# PCBSchematic.net
KiCad netlist of a schematic drawn in Altium Designer
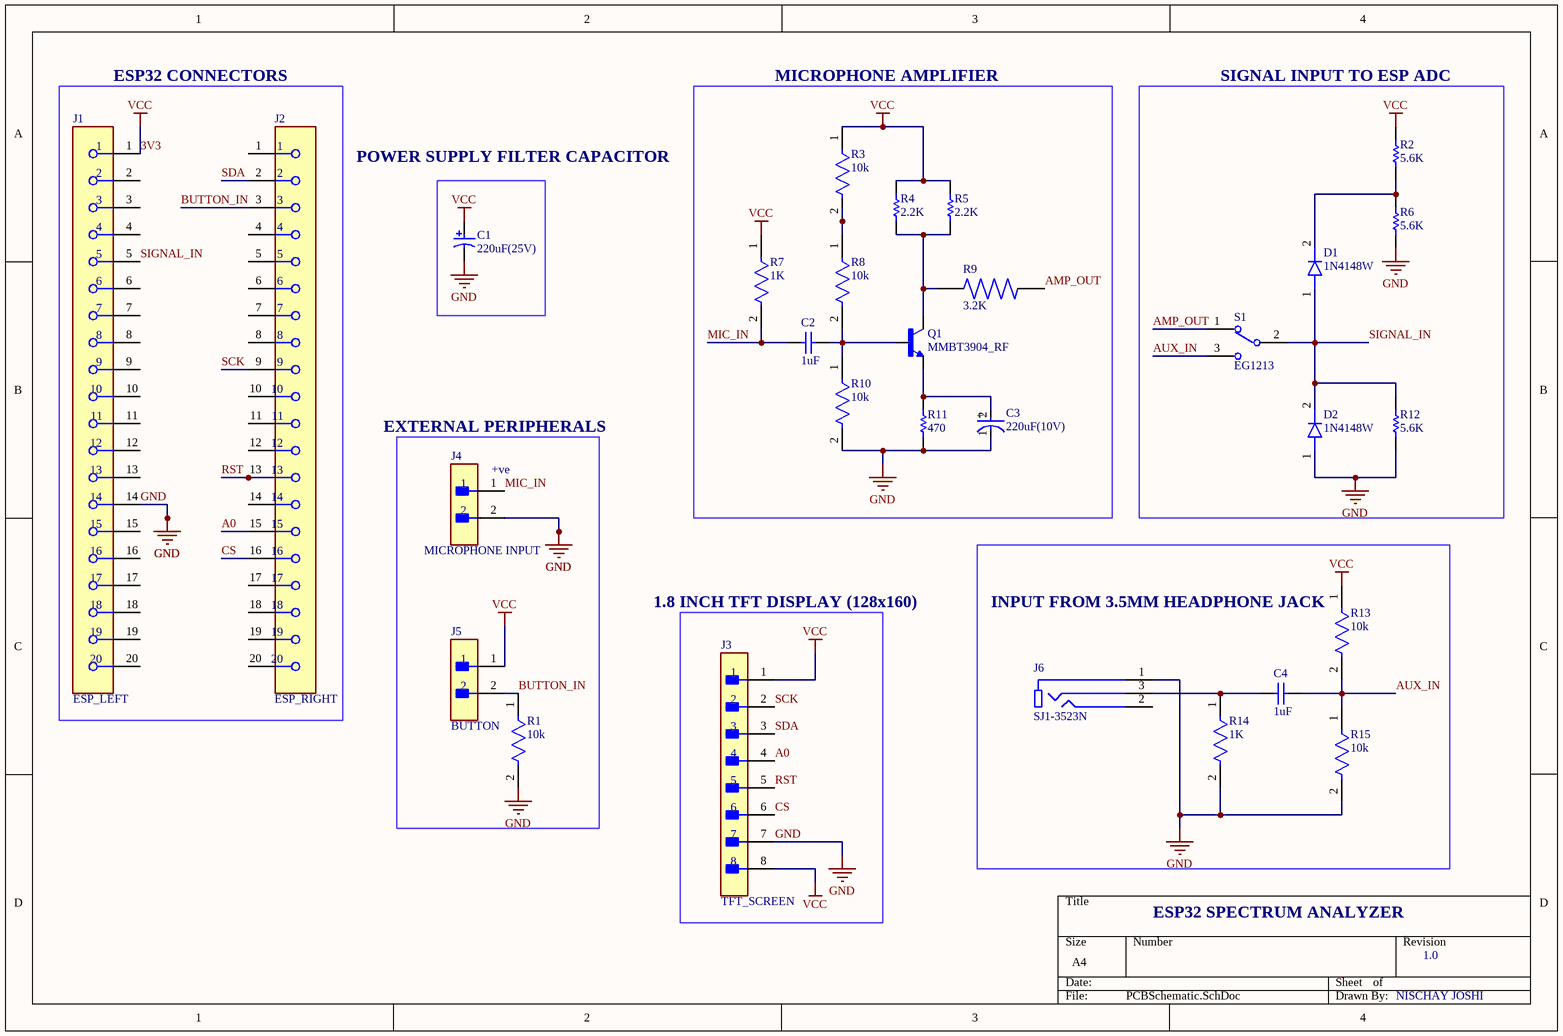
[diagram p0: PCBSchematic.SchDoc]

(export (version "E")
  (design (tool "Eeschema 10.0.6"))
  (components
    (comp (ref "C1")
      (value "220uF(25V)")
      (footprint "PNSC-EEE-FK1E221P_N")
      (fields (field (name "MANUFACTURER") "Panasonic"))
      (libsource (lib "Altium Content Vault") (part "CAP-P-2"))
    )
    (comp (ref "C2")
      (value "1uF")
      (footprint "CAPC3216X110X50LL20T25")
      (description "Chip Capacitor, 1 uF, +/- 10%, 50 V, -55 to 125 degC, 1206 (3216 Metric), RoHS, Tape and Reel")
      (fields (field (name "MANUFACTURER") "Kemet") (field (name "TOLERANCE") "10%"))
      (libsource (lib "Altium Content Vault") (part "CAP-NP-2"))
    )
    (comp (ref "C3")
      (value "220uF(10V)")
      (footprint "FP-TAJD-MFG")
      (description "220uF 10V  ±10% 500mΩ 2917  SMD Tantalum Capacitor")
      (fields (field (name "TOLERANCE") "10%") (field (name "VOLTAGE") "10V"))
      (libsource (lib "Altium Content Vault") (part "a00bbbee19879c290e62620ae7e47b1"))
    )
    (comp (ref "C4")
      (value "1uF")
      (footprint "CAPC3216X110X50LL20T25")
      (description "Chip Capacitor, 1 uF, +/- 10%, 50 V, -55 to 125 degC, 1206 (3216 Metric), RoHS, Tape and Reel")
      (fields (field (name "MANUFACTURER") "Kemet") (field (name "TOLERANCE") "10%"))
      (libsource (lib "Altium Content Vault") (part "CAP-NP-2"))
    )
    (comp (ref "D1")
      (value "1N4148W")
      (footprint "1N4148W:SOD523F")
      (fields (field (name "MF") "{'manufacturer': u'Diotec Semiconductor'}"))
      (libsource (lib "*") (part "1N4148W"))
    )
    (comp (ref "D2")
      (value "1N4148W")
      (footprint "1N4148W:SOD523F")
      (fields (field (name "MF") "{'manufacturer': u'Diotec Semiconductor'}"))
      (libsource (lib "*") (part "1N4148W"))
    )
    (comp (ref "J1")
      (value "ESP_LEFT")
      (footprint "FP-ESQ-120-14-G-S-MFG")
      (description "CONN SOCKET 20POS 0.1 GOLD PCB")
      (libsource (lib "Altium Content Vault") (part "dba14e038e6f7492952b7f1e871f183"))
    )
    (comp (ref "J2")
      (value "ESP_RIGHT")
      (footprint "FP-ESQ-120-14-G-S-MFG")
      (description "CONN SOCKET 20POS 0.1 GOLD PCB")
      (libsource (lib "Altium Content Vault") (part "dba14e038e6f7492952b7f1e871f183"))
    )
    (comp (ref "J3")
      (value "TFT_SCREEN")
      (footprint "FP-M20-9990846-MFG")
      (description "CONN HEADER VERT 8POS 2.54MM")
      (libsource (lib "Altium Content Vault") (part "99ec2b232beb5d2356d4d77f6a047f0"))
    )
    (comp (ref "J4")
      (value "MICROPHONE INPUT")
      (footprint "FP-M20-9990246-MFG")
      (description "CONN HEADER VERT 2POS 2.54MM")
      (fields
        (field (name "OCTOPART") "https://octopart.com/m20-9990246-harwin-2590635")
        (field (name "MANUFACTURER") "Harwin")
      )
      (libsource (lib "Altium Content Vault") (part "3bc925449376181038e59eaffc5286c"))
    )
    (comp (ref "J5")
      (value "BUTTON")
      (footprint "FP-M20-9990246-MFG")
      (description "CONN HEADER VERT 2POS 2.54MM")
      (fields
        (field (name "OCTOPART") "https://octopart.com/m20-9990246-harwin-2590635")
        (field (name "MANUFACTURER") "Harwin")
      )
      (libsource (lib "Altium Content Vault") (part "3bc925449376181038e59eaffc5286c"))
    )
    (comp (ref "J6")
      (value "SJ1-3523N")
      (footprint "SJ1-3523N:CUI_SJ1-3523N")
      (description "3.5 mm Right-Angle Stereo Jack, 3 Pin PCB Mount, Non-Threaded")
      (fields (field (name "MF") "{'manufacturer': u'CUI Devices'}"))
      (libsource (lib "*") (part "SJ1-3523N"))
    )
    (comp (ref "Q1")
      (value "MMBT3904_RF")
      (footprint "MMBT3904 RF:SOT95P237X112-3N")
      (description "Bipolar (BJT) Transistor NPN 65 V 100 mA 100MHz 200 mW Surface Mount SOT-23")
      (fields (field (name "MF") "{'manufacturer': u'Taiwan Semiconductor'}"))
      (libsource (lib "*") (part "MMBT3904_RF"))
    )
    (comp (ref "R1")
      (value "10k")
      (footprint "FP-RMCF2512-IPC_C")
      (description "10kΩ ±5% 1W 2512 Thick Film Chip Resistor AEC-Q200 compliant")
      (fields (field (name "TOLERANCE") "5%"))
      (libsource (lib "Altium Content Vault") (part "1029c3af85768c4190bb7ad29bc67b5"))
    )
    (comp (ref "R2")
      (value "5.6K")
      (footprint "RESC3216X60X45LL10T20")
      (fields (field (name "MANUFACTURER") "Vishay Dale") (field (name "PART NUMBER") "CRCW12065K60FKEA"))
      (libsource (lib "Altium Content Vault") (part "RES"))
    )
    (comp (ref "R3")
      (value "10k")
      (footprint "FP-RMCF2512-IPC_C")
      (description "10kΩ ±5% 1W 2512 Thick Film Chip Resistor AEC-Q200 compliant")
      (fields (field (name "TOLERANCE") "5%"))
      (libsource (lib "Altium Content Vault") (part "1029c3af85768c4190bb7ad29bc67b5"))
    )
    (comp (ref "R4")
      (value "2.2K")
      (footprint "RESC3116X65X40ML10T20")
      (description "Chip Resistor, 2.2 KOhm, +/- 1%, 250 mW, -55 to 155 degC, 1206 (3216 Metric), RoHS, Tape and Reel")
      (fields (field (name "MANUFACTURER") "Yageo") (field (name "TOLERANCE") "1%"))
      (libsource (lib "Altium Content Vault") (part "RES-2"))
    )
    (comp (ref "R5")
      (value "2.2K")
      (footprint "RESC3116X65X40ML10T20")
      (description "Chip Resistor, 2.2 KOhm, +/- 1%, 250 mW, -55 to 155 degC, 1206 (3216 Metric), RoHS, Tape and Reel")
      (fields (field (name "MANUFACTURER") "Yageo") (field (name "TOLERANCE") "1%"))
      (libsource (lib "Altium Content Vault") (part "RES-2"))
    )
    (comp (ref "R6")
      (value "5.6K")
      (footprint "RESC3216X60X45LL10T20")
      (fields (field (name "MANUFACTURER") "Vishay Dale") (field (name "PART NUMBER") "CRCW12065K60FKEA"))
      (libsource (lib "Altium Content Vault") (part "RES"))
    )
    (comp (ref "R7")
      (value "1K")
      (footprint "FP-CRCW2512-e3-IPC_C")
      (description "RES Thick Film, 1kΩ, 1%, 1W, 100ppm/°C, 2512")
      (fields (field (name "TOLERANCE") "1%"))
      (libsource (lib "Altium Content Vault") (part "1029c3af85768c4190bb7ad29bc67b5"))
    )
    (comp (ref "R8")
      (value "10k")
      (footprint "FP-RMCF2512-IPC_C")
      (description "10kΩ ±5% 1W 2512 Thick Film Chip Resistor AEC-Q200 compliant")
      (fields (field (name "TOLERANCE") "5%"))
      (libsource (lib "Altium Content Vault") (part "1029c3af85768c4190bb7ad29bc67b5"))
    )
    (comp (ref "R9")
      (value "3.2K")
      (footprint "TNPW12063K20BEEN:RESC3116X65N")
      (description "3.2K OHM .1% 25PPM")
      (fields (field (name "MP") "TNPW12063K20BEEN") (field (name "MF") "{'manufacturer': u'Vishay'}"))
      (libsource (lib "*") (part "TNPW12063K20BEEN"))
    )
    (comp (ref "R10")
      (value "10k")
      (footprint "FP-RMCF2512-IPC_C")
      (description "10kΩ ±5% 1W 2512 Thick Film Chip Resistor AEC-Q200 compliant")
      (fields (field (name "TOLERANCE") "5%"))
      (libsource (lib "Altium Content Vault") (part "1029c3af85768c4190bb7ad29bc67b5"))
    )
    (comp (ref "R11")
      (value "470")
      (footprint "RESC3216X60X45ML10T20")
      (fields (field (name "MANUFACTURER") "Vishay Dale") (field (name "PART NUMBER") "CRCW1206470RFKEA"))
      (libsource (lib "Altium Content Vault") (part "RES"))
    )
    (comp (ref "R12")
      (value "5.6K")
      (footprint "RESC3216X60X45LL10T20")
      (fields (field (name "MANUFACTURER") "Vishay Dale") (field (name "PART NUMBER") "CRCW12065K60FKEA"))
      (libsource (lib "Altium Content Vault") (part "RES"))
    )
    (comp (ref "R13")
      (value "10k")
      (footprint "FP-RMCF2512-IPC_C")
      (description "10kΩ ±5% 1W 2512 Thick Film Chip Resistor AEC-Q200 compliant")
      (fields (field (name "TOLERANCE") "5%"))
      (libsource (lib "Altium Content Vault") (part "1029c3af85768c4190bb7ad29bc67b5"))
    )
    (comp (ref "R14")
      (value "1K")
      (footprint "FP-CRCW2512-e3-IPC_C")
      (description "RES Thick Film, 1kΩ, 1%, 1W, 100ppm/°C, 2512")
      (fields (field (name "TOLERANCE") "1%"))
      (libsource (lib "Altium Content Vault") (part "1029c3af85768c4190bb7ad29bc67b5"))
    )
    (comp (ref "R15")
      (value "10k")
      (footprint "FP-RMCF2512-IPC_C")
      (description "10kΩ ±5% 1W 2512 Thick Film Chip Resistor AEC-Q200 compliant")
      (fields (field (name "TOLERANCE") "5%"))
      (libsource (lib "Altium Content Vault") (part "1029c3af85768c4190bb7ad29bc67b5"))
    )
    (comp (ref "S1")
      (value "EG1213")
      (footprint "EG1213:SW_EG1213")
      (description "<b>EG Series SPDT On-On Right Angle Through Hole Slide Switch</b>")
      (fields (field (name "MF") "{'manufacturer': u'E-Switch'}"))
      (libsource (lib "*") (part "EG1213"))
    )
  )
  (nets
    (net (code "1") (name "/A0") (class "Default")
      (node (ref "J2") (pin "15") (pinfunction "15_15") (pintype "passive"))
      (node (ref "J3") (pin "4") (pinfunction "4_4") (pintype "passive"))
    )
    (net (code "2") (name "/AMP_OUT") (class "Default")
      (node (ref "R9") (pin "2") (pinfunction "2_2") (pintype "passive"))
      (node (ref "S1") (pin "1") (pinfunction "1_1") (pintype "passive"))
    )
    (net (code "3") (name "/AUX_IN") (class "Default")
      (node (ref "C4") (pin "2") (pinfunction "2_2") (pintype "passive"))
      (node (ref "R13") (pin "2") (pinfunction "2_2") (pintype "passive"))
      (node (ref "R15") (pin "1") (pinfunction "1_1") (pintype "passive"))
      (node (ref "S1") (pin "3") (pinfunction "3_3") (pintype "passive"))
    )
    (net (code "4") (name "/BUTTON_IN") (class "Default")
      (node (ref "J2") (pin "3") (pinfunction "3_3") (pintype "passive"))
      (node (ref "J5") (pin "2") (pinfunction "2_2") (pintype "passive"))
      (node (ref "R1") (pin "1") (pinfunction "1_1") (pintype "passive"))
    )
    (net (code "5") (name "/CS") (class "Default")
      (node (ref "J2") (pin "16") (pinfunction "16_16") (pintype "passive"))
      (node (ref "J3") (pin "6") (pinfunction "6_6") (pintype "passive"))
    )
    (net (code "6") (name "/MIC_IN") (class "Default")
      (node (ref "C2") (pin "1") (pinfunction "1_1") (pintype "passive"))
      (node (ref "J4") (pin "1") (pinfunction "1_1") (pintype "passive"))
      (node (ref "R7") (pin "2") (pinfunction "2_2") (pintype "passive"))
    )
    (net (code "7") (name "/RST") (class "Default")
      (node (ref "J2") (pin "13") (pinfunction "13_13") (pintype "passive"))
      (node (ref "J3") (pin "5") (pinfunction "5_5") (pintype "passive"))
    )
    (net (code "8") (name "/SCK") (class "Default")
      (node (ref "J2") (pin "9") (pinfunction "9_9") (pintype "passive"))
      (node (ref "J3") (pin "2") (pinfunction "2_2") (pintype "passive"))
    )
    (net (code "9") (name "/SDA") (class "Default")
      (node (ref "J2") (pin "2") (pinfunction "2_2") (pintype "passive"))
      (node (ref "J3") (pin "3") (pinfunction "3_3") (pintype "passive"))
    )
    (net (code "10") (name "/SIGNAL_IN") (class "Default")
      (node (ref "D1") (pin "1") (pinfunction "A1_1") (pintype "passive"))
      (node (ref "D2") (pin "2") (pinfunction "C1_2") (pintype "passive"))
      (node (ref "J1") (pin "5") (pinfunction "5_5") (pintype "passive"))
      (node (ref "R12") (pin "2") (pinfunction "2_2") (pintype "passive"))
      (node (ref "S1") (pin "2") (pinfunction "2_2") (pintype "passive"))
    )
    (net (code "11") (name "GND") (class "Default")
      (node (ref "C1") (pin "2") (pinfunction "2_2") (pintype "passive"))
      (node (ref "C3") (pin "1") (pinfunction "C_1") (pintype "passive"))
      (node (ref "D2") (pin "1") (pinfunction "A1_1") (pintype "passive"))
      (node (ref "J1") (pin "14") (pinfunction "14_14") (pintype "passive"))
      (node (ref "J3") (pin "7") (pinfunction "7_7") (pintype "passive"))
      (node (ref "J4") (pin "2") (pinfunction "2_2") (pintype "passive"))
      (node (ref "J6") (pin "1") (pinfunction "1_1") (pintype "passive"))
      (node (ref "R1") (pin "2") (pinfunction "2_2") (pintype "passive"))
      (node (ref "R10") (pin "2") (pinfunction "2_2") (pintype "passive"))
      (node (ref "R11") (pin "1") (pinfunction "1_1") (pintype "passive"))
      (node (ref "R12") (pin "1") (pinfunction "1_1") (pintype "passive"))
      (node (ref "R14") (pin "2") (pinfunction "2_2") (pintype "passive"))
      (node (ref "R15") (pin "2") (pinfunction "2_2") (pintype "passive"))
      (node (ref "R6") (pin "1") (pinfunction "1_1") (pintype "passive"))
    )
    (net (code "12") (name "Net-(C3-A)") (class "Default")
      (node (ref "C3") (pin "2") (pinfunction "A_2") (pintype "passive"))
      (node (ref "Q1") (pin "2") (pinfunction "E_2") (pintype "passive"))
      (node (ref "R11") (pin "2") (pinfunction "2_2") (pintype "passive"))
    )
    (net (code "13") (name "Net-(C4-Pad1)") (class "Default")
      (node (ref "C4") (pin "1") (pinfunction "1_1") (pintype "passive"))
      (node (ref "J6") (pin "3") (pinfunction "3_3") (pintype "passive"))
      (node (ref "R14") (pin "1") (pinfunction "1_1") (pintype "passive"))
    )
    (net (code "14") (name "Net-(D1-C1)") (class "Default")
      (node (ref "D1") (pin "2") (pinfunction "C1_2") (pintype "passive"))
      (node (ref "R2") (pin "1") (pinfunction "1_1") (pintype "passive"))
      (node (ref "R6") (pin "2") (pinfunction "2_2") (pintype "passive"))
    )
    (net (code "15") (name "Net-(Q1-B)") (class "Default")
      (node (ref "C2") (pin "2") (pinfunction "2_2") (pintype "passive"))
      (node (ref "Q1") (pin "1") (pinfunction "B_1") (pintype "passive"))
      (node (ref "R10") (pin "1") (pinfunction "1_1") (pintype "passive"))
      (node (ref "R8") (pin "2") (pinfunction "2_2") (pintype "passive"))
    )
    (net (code "16") (name "Net-(Q1-C)") (class "Default")
      (node (ref "Q1") (pin "3") (pinfunction "C_3") (pintype "passive"))
      (node (ref "R4") (pin "1") (pinfunction "1_1") (pintype "passive"))
      (node (ref "R5") (pin "1") (pinfunction "1_1") (pintype "passive"))
      (node (ref "R9") (pin "1") (pinfunction "1_1") (pintype "passive"))
    )
    (net (code "17") (name "Net-(R3-Pad2)") (class "Default")
      (node (ref "R3") (pin "2") (pinfunction "2_2") (pintype "passive"))
      (node (ref "R8") (pin "1") (pinfunction "1_1") (pintype "passive"))
    )
    (net (code "18") (name "VCC") (class "Default")
      (node (ref "C1") (pin "1") (pinfunction "1_1") (pintype "passive"))
      (node (ref "J1") (pin "1") (pinfunction "1_1") (pintype "passive"))
      (node (ref "J3") (pin "1") (pinfunction "1_1") (pintype "passive"))
      (node (ref "J3") (pin "8") (pinfunction "8_8") (pintype "passive"))
      (node (ref "J5") (pin "1") (pinfunction "1_1") (pintype "passive"))
      (node (ref "R13") (pin "1") (pinfunction "1_1") (pintype "passive"))
      (node (ref "R2") (pin "2") (pinfunction "2_2") (pintype "passive"))
      (node (ref "R3") (pin "1") (pinfunction "1_1") (pintype "passive"))
      (node (ref "R4") (pin "2") (pinfunction "2_2") (pintype "passive"))
      (node (ref "R5") (pin "2") (pinfunction "2_2") (pintype "passive"))
      (node (ref "R7") (pin "1") (pinfunction "1_1") (pintype "passive"))
    )
    (net (code "19") (name "unconnected-(J1-Pad2)") (class "Default")
      (node (ref "J1") (pin "2") (pinfunction "2_2") (pintype "passive"))
    )
    (net (code "20") (name "unconnected-(J1-Pad3)") (class "Default")
      (node (ref "J1") (pin "3") (pinfunction "3_3") (pintype "passive"))
    )
    (net (code "21") (name "unconnected-(J1-Pad4)") (class "Default")
      (node (ref "J1") (pin "4") (pinfunction "4_4") (pintype "passive"))
    )
    (net (code "22") (name "unconnected-(J1-Pad6)") (class "Default")
      (node (ref "J1") (pin "6") (pinfunction "6_6") (pintype "passive"))
    )
    (net (code "23") (name "unconnected-(J1-Pad7)") (class "Default")
      (node (ref "J1") (pin "7") (pinfunction "7_7") (pintype "passive"))
    )
    (net (code "24") (name "unconnected-(J1-Pad8)") (class "Default")
      (node (ref "J1") (pin "8") (pinfunction "8_8") (pintype "passive"))
    )
    (net (code "25") (name "unconnected-(J1-Pad9)") (class "Default")
      (node (ref "J1") (pin "9") (pinfunction "9_9") (pintype "passive"))
    )
    (net (code "26") (name "unconnected-(J1-Pad10)") (class "Default")
      (node (ref "J1") (pin "10") (pinfunction "10_10") (pintype "passive"))
    )
    (net (code "27") (name "unconnected-(J1-Pad11)") (class "Default")
      (node (ref "J1") (pin "11") (pinfunction "11_11") (pintype "passive"))
    )
    (net (code "28") (name "unconnected-(J1-Pad12)") (class "Default")
      (node (ref "J1") (pin "12") (pinfunction "12_12") (pintype "passive"))
    )
    (net (code "29") (name "unconnected-(J1-Pad13)") (class "Default")
      (node (ref "J1") (pin "13") (pinfunction "13_13") (pintype "passive"))
    )
    (net (code "30") (name "unconnected-(J1-Pad15)") (class "Default")
      (node (ref "J1") (pin "15") (pinfunction "15_15") (pintype "passive"))
    )
    (net (code "31") (name "unconnected-(J1-Pad16)") (class "Default")
      (node (ref "J1") (pin "16") (pinfunction "16_16") (pintype "passive"))
    )
    (net (code "32") (name "unconnected-(J1-Pad17)") (class "Default")
      (node (ref "J1") (pin "17") (pinfunction "17_17") (pintype "passive"))
    )
    (net (code "33") (name "unconnected-(J1-Pad18)") (class "Default")
      (node (ref "J1") (pin "18") (pinfunction "18_18") (pintype "passive"))
    )
    (net (code "34") (name "unconnected-(J1-Pad19)") (class "Default")
      (node (ref "J1") (pin "19") (pinfunction "19_19") (pintype "passive"))
    )
    (net (code "35") (name "unconnected-(J1-Pad20)") (class "Default")
      (node (ref "J1") (pin "20") (pinfunction "20_20") (pintype "passive"))
    )
    (net (code "36") (name "unconnected-(J2-Pad1)") (class "Default")
      (node (ref "J2") (pin "1") (pinfunction "1_1") (pintype "passive"))
    )
    (net (code "37") (name "unconnected-(J2-Pad4)") (class "Default")
      (node (ref "J2") (pin "4") (pinfunction "4_4") (pintype "passive"))
    )
    (net (code "38") (name "unconnected-(J2-Pad5)") (class "Default")
      (node (ref "J2") (pin "5") (pinfunction "5_5") (pintype "passive"))
    )
    (net (code "39") (name "unconnected-(J2-Pad6)") (class "Default")
      (node (ref "J2") (pin "6") (pinfunction "6_6") (pintype "passive"))
    )
    (net (code "40") (name "unconnected-(J2-Pad7)") (class "Default")
      (node (ref "J2") (pin "7") (pinfunction "7_7") (pintype "passive"))
    )
    (net (code "41") (name "unconnected-(J2-Pad8)") (class "Default")
      (node (ref "J2") (pin "8") (pinfunction "8_8") (pintype "passive"))
    )
    (net (code "42") (name "unconnected-(J2-Pad10)") (class "Default")
      (node (ref "J2") (pin "10") (pinfunction "10_10") (pintype "passive"))
    )
    (net (code "43") (name "unconnected-(J2-Pad11)") (class "Default")
      (node (ref "J2") (pin "11") (pinfunction "11_11") (pintype "passive"))
    )
    (net (code "44") (name "unconnected-(J2-Pad12)") (class "Default")
      (node (ref "J2") (pin "12") (pinfunction "12_12") (pintype "passive"))
    )
    (net (code "45") (name "unconnected-(J2-Pad14)") (class "Default")
      (node (ref "J2") (pin "14") (pinfunction "14_14") (pintype "passive"))
    )
    (net (code "46") (name "unconnected-(J2-Pad17)") (class "Default")
      (node (ref "J2") (pin "17") (pinfunction "17_17") (pintype "passive"))
    )
    (net (code "47") (name "unconnected-(J2-Pad18)") (class "Default")
      (node (ref "J2") (pin "18") (pinfunction "18_18") (pintype "passive"))
    )
    (net (code "48") (name "unconnected-(J2-Pad19)") (class "Default")
      (node (ref "J2") (pin "19") (pinfunction "19_19") (pintype "passive"))
    )
    (net (code "49") (name "unconnected-(J2-Pad20)") (class "Default")
      (node (ref "J2") (pin "20") (pinfunction "20_20") (pintype "passive"))
    )
    (net (code "50") (name "unconnected-(J6-Pad2)") (class "Default")
      (node (ref "J6") (pin "2") (pinfunction "2_2") (pintype "passive"))
    )
  )
)
